# led_board.net
KiCad netlist of a schematic drawn in EAGLE
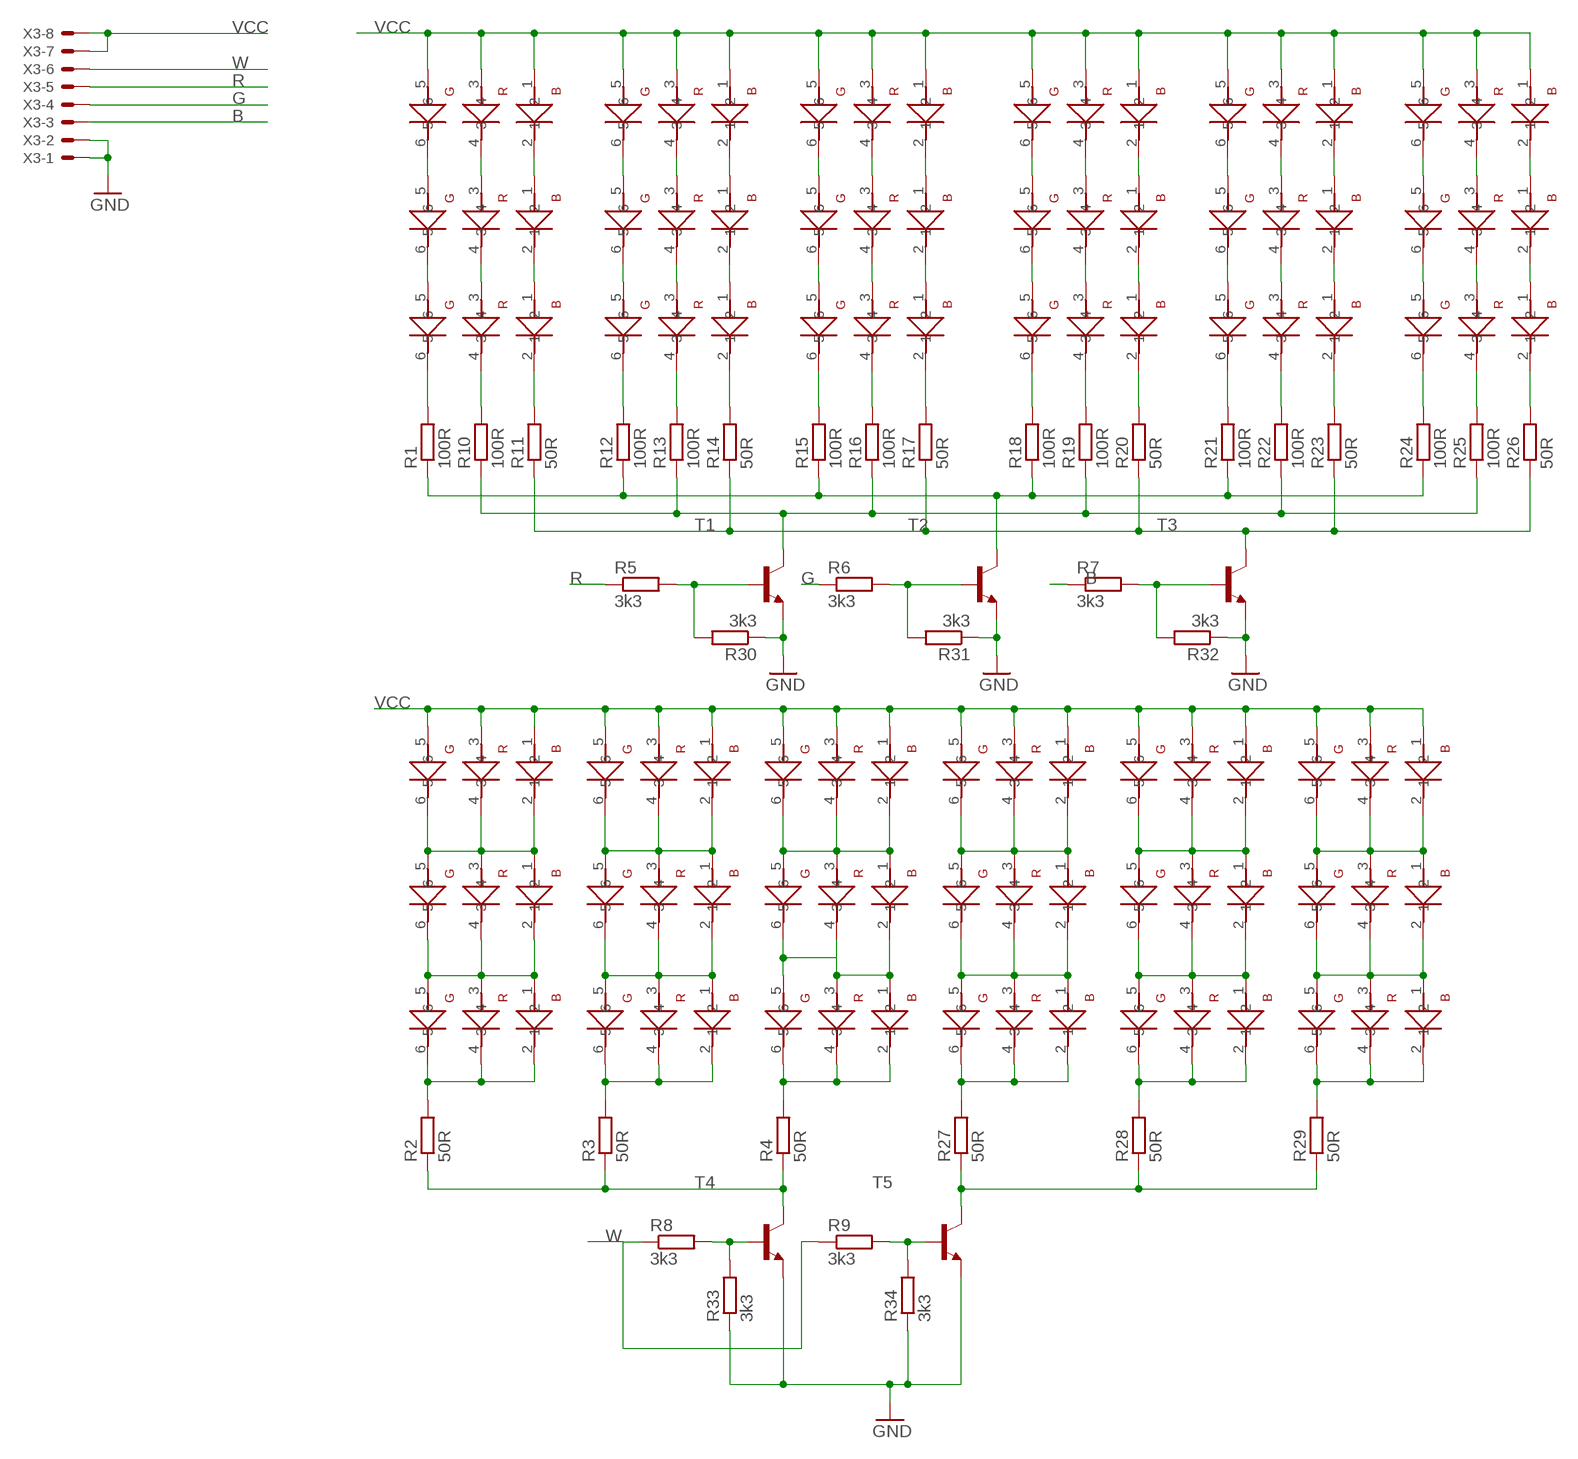
[diagram p0: schematic, sheet 1]

(export (version "E")
  (design (tool "Eeschema 10.0.6"))
  (components
    (comp (ref "R1")
      (value "100R")
      (footprint "eagle-import:M1206")
      (libsource (lib "eagle-import") (part "R-EU_M1206"))
    )
    (comp (ref "R2")
      (value "50R")
      (footprint "eagle-import:M1206")
      (libsource (lib "eagle-import") (part "R-EU_M1206"))
    )
    (comp (ref "R3")
      (value "50R")
      (footprint "eagle-import:M1206")
      (libsource (lib "eagle-import") (part "R-EU_M1206"))
    )
    (comp (ref "R4")
      (value "50R")
      (footprint "eagle-import:M1206")
      (libsource (lib "eagle-import") (part "R-EU_M1206"))
    )
    (comp (ref "R5")
      (value "3k3")
      (footprint "eagle-import:M1206")
      (libsource (lib "eagle-import") (part "R-EU_M1206"))
    )
    (comp (ref "R6")
      (value "3k3")
      (footprint "eagle-import:M1206")
      (libsource (lib "eagle-import") (part "R-EU_M1206"))
    )
    (comp (ref "R7")
      (value "3k3")
      (footprint "eagle-import:M1206")
      (libsource (lib "eagle-import") (part "R-EU_M1206"))
    )
    (comp (ref "R8")
      (value "3k3")
      (footprint "eagle-import:M1206")
      (libsource (lib "eagle-import") (part "R-EU_M1206"))
    )
    (comp (ref "R9")
      (value "3k3")
      (footprint "eagle-import:M1206")
      (libsource (lib "eagle-import") (part "R-EU_M1206"))
    )
    (comp (ref "R10")
      (value "100R")
      (footprint "eagle-import:M1206")
      (libsource (lib "eagle-import") (part "R-EU_M1206"))
    )
    (comp (ref "R11")
      (value "50R")
      (footprint "eagle-import:M1206")
      (libsource (lib "eagle-import") (part "R-EU_M1206"))
    )
    (comp (ref "R12")
      (value "100R")
      (footprint "eagle-import:M1206")
      (libsource (lib "eagle-import") (part "R-EU_M1206"))
    )
    (comp (ref "R13")
      (value "100R")
      (footprint "eagle-import:M1206")
      (libsource (lib "eagle-import") (part "R-EU_M1206"))
    )
    (comp (ref "R14")
      (value "50R")
      (footprint "eagle-import:M1206")
      (libsource (lib "eagle-import") (part "R-EU_M1206"))
    )
    (comp (ref "R15")
      (value "100R")
      (footprint "eagle-import:M1206")
      (libsource (lib "eagle-import") (part "R-EU_M1206"))
    )
    (comp (ref "R16")
      (value "100R")
      (footprint "eagle-import:M1206")
      (libsource (lib "eagle-import") (part "R-EU_M1206"))
    )
    (comp (ref "R17")
      (value "50R")
      (footprint "eagle-import:M1206")
      (libsource (lib "eagle-import") (part "R-EU_M1206"))
    )
    (comp (ref "R18")
      (value "100R")
      (footprint "eagle-import:M1206")
      (libsource (lib "eagle-import") (part "R-EU_M1206"))
    )
    (comp (ref "R19")
      (value "100R")
      (footprint "eagle-import:M1206")
      (libsource (lib "eagle-import") (part "R-EU_M1206"))
    )
    (comp (ref "R20")
      (value "50R")
      (footprint "eagle-import:M1206")
      (libsource (lib "eagle-import") (part "R-EU_M1206"))
    )
    (comp (ref "R21")
      (value "100R")
      (footprint "eagle-import:M1206")
      (libsource (lib "eagle-import") (part "R-EU_M1206"))
    )
    (comp (ref "R22")
      (value "100R")
      (footprint "eagle-import:M1206")
      (libsource (lib "eagle-import") (part "R-EU_M1206"))
    )
    (comp (ref "R23")
      (value "50R")
      (footprint "eagle-import:M1206")
      (libsource (lib "eagle-import") (part "R-EU_M1206"))
    )
    (comp (ref "R24")
      (value "100R")
      (footprint "eagle-import:M1206")
      (libsource (lib "eagle-import") (part "R-EU_M1206"))
    )
    (comp (ref "R25")
      (value "100R")
      (footprint "eagle-import:M1206")
      (libsource (lib "eagle-import") (part "R-EU_M1206"))
    )
    (comp (ref "R26")
      (value "50R")
      (footprint "eagle-import:M1206")
      (libsource (lib "eagle-import") (part "R-EU_M1206"))
    )
    (comp (ref "R27")
      (value "50R")
      (footprint "eagle-import:M1206")
      (libsource (lib "eagle-import") (part "R-EU_M1206"))
    )
    (comp (ref "R28")
      (value "50R")
      (footprint "eagle-import:M1206")
      (libsource (lib "eagle-import") (part "R-EU_M1206"))
    )
    (comp (ref "R29")
      (value "50R")
      (footprint "eagle-import:M1206")
      (libsource (lib "eagle-import") (part "R-EU_M1206"))
    )
    (comp (ref "R30")
      (value "3k3")
      (footprint "eagle-import:M1206")
      (libsource (lib "eagle-import") (part "R-EU_M1206"))
    )
    (comp (ref "R31")
      (value "3k3")
      (footprint "eagle-import:M1206")
      (libsource (lib "eagle-import") (part "R-EU_M1206"))
    )
    (comp (ref "R32")
      (value "3k3")
      (footprint "eagle-import:M1206")
      (libsource (lib "eagle-import") (part "R-EU_M1206"))
    )
    (comp (ref "R33")
      (value "3k3")
      (footprint "eagle-import:M1206")
      (libsource (lib "eagle-import") (part "R-EU_M1206"))
    )
    (comp (ref "R34")
      (value "3k3")
      (footprint "eagle-import:M1206")
      (libsource (lib "eagle-import") (part "R-EU_M1206"))
    )
    (comp (ref "T1")
      (value "-NPN-SOT223")
      (footprint "eagle-import:SOT223")
      (libsource (lib "eagle-import") (part "-NPN-SOT223"))
    )
    (comp (ref "T2")
      (value "-NPN-SOT223")
      (footprint "eagle-import:SOT223")
      (libsource (lib "eagle-import") (part "-NPN-SOT223"))
    )
    (comp (ref "T3")
      (value "-NPN-SOT223")
      (footprint "eagle-import:SOT223")
      (libsource (lib "eagle-import") (part "-NPN-SOT223"))
    )
    (comp (ref "T4")
      (value "-NPN-SOT223")
      (footprint "eagle-import:SOT223")
      (libsource (lib "eagle-import") (part "-NPN-SOT223"))
    )
    (comp (ref "T5")
      (value "-NPN-SOT223")
      (footprint "eagle-import:SOT223")
      (libsource (lib "eagle-import") (part "-NPN-SOT223"))
    )
    (comp (ref "U$1")
      (value "5050_LED")
      (footprint "eagle-import:5050_LED")
      (libsource (lib "eagle-import") (part "5050_LED"))
    )
    (comp (ref "U$2")
      (value "5050_LED")
      (footprint "eagle-import:5050_LED")
      (libsource (lib "eagle-import") (part "5050_LED"))
    )
    (comp (ref "U$3")
      (value "5050_LED")
      (footprint "eagle-import:5050_LED")
      (libsource (lib "eagle-import") (part "5050_LED"))
    )
    (comp (ref "U$4")
      (value "5050_LED")
      (footprint "eagle-import:5050_LED")
      (libsource (lib "eagle-import") (part "5050_LED"))
    )
    (comp (ref "U$5")
      (value "5050_LED")
      (footprint "eagle-import:5050_LED")
      (libsource (lib "eagle-import") (part "5050_LED"))
    )
    (comp (ref "U$6")
      (value "5050_LED")
      (footprint "eagle-import:5050_LED")
      (libsource (lib "eagle-import") (part "5050_LED"))
    )
    (comp (ref "U$7")
      (value "5050_LED")
      (footprint "eagle-import:5050_LED")
      (libsource (lib "eagle-import") (part "5050_LED"))
    )
    (comp (ref "U$8")
      (value "5050_LED")
      (footprint "eagle-import:5050_LED")
      (libsource (lib "eagle-import") (part "5050_LED"))
    )
    (comp (ref "U$9")
      (value "5050_LED")
      (footprint "eagle-import:5050_LED")
      (libsource (lib "eagle-import") (part "5050_LED"))
    )
    (comp (ref "U$10")
      (value "5050_LED")
      (footprint "eagle-import:5050_LED")
      (libsource (lib "eagle-import") (part "5050_LED"))
    )
    (comp (ref "U$11")
      (value "5050_LED")
      (footprint "eagle-import:5050_LED")
      (libsource (lib "eagle-import") (part "5050_LED"))
    )
    (comp (ref "U$12")
      (value "5050_LED")
      (footprint "eagle-import:5050_LED")
      (libsource (lib "eagle-import") (part "5050_LED"))
    )
    (comp (ref "U$13")
      (value "5050_LED")
      (footprint "eagle-import:5050_LED")
      (libsource (lib "eagle-import") (part "5050_LED"))
    )
    (comp (ref "U$14")
      (value "5050_LED")
      (footprint "eagle-import:5050_LED")
      (libsource (lib "eagle-import") (part "5050_LED"))
    )
    (comp (ref "U$15")
      (value "5050_LED")
      (footprint "eagle-import:5050_LED")
      (libsource (lib "eagle-import") (part "5050_LED"))
    )
    (comp (ref "U$16")
      (value "5050_LED")
      (footprint "eagle-import:5050_LED")
      (libsource (lib "eagle-import") (part "5050_LED"))
    )
    (comp (ref "U$17")
      (value "5050_LED")
      (footprint "eagle-import:5050_LED")
      (libsource (lib "eagle-import") (part "5050_LED"))
    )
    (comp (ref "U$18")
      (value "5050_LED")
      (footprint "eagle-import:5050_LED")
      (libsource (lib "eagle-import") (part "5050_LED"))
    )
    (comp (ref "U$19")
      (value "5050_LED")
      (footprint "eagle-import:5050_LED")
      (libsource (lib "eagle-import") (part "5050_LED"))
    )
    (comp (ref "U$20")
      (value "5050_LED")
      (footprint "eagle-import:5050_LED")
      (libsource (lib "eagle-import") (part "5050_LED"))
    )
    (comp (ref "U$21")
      (value "5050_LED")
      (footprint "eagle-import:5050_LED")
      (libsource (lib "eagle-import") (part "5050_LED"))
    )
    (comp (ref "U$22")
      (value "5050_LED")
      (footprint "eagle-import:5050_LED")
      (libsource (lib "eagle-import") (part "5050_LED"))
    )
    (comp (ref "U$23")
      (value "5050_LED")
      (footprint "eagle-import:5050_LED")
      (libsource (lib "eagle-import") (part "5050_LED"))
    )
    (comp (ref "U$24")
      (value "5050_LED")
      (footprint "eagle-import:5050_LED")
      (libsource (lib "eagle-import") (part "5050_LED"))
    )
    (comp (ref "U$25")
      (value "5050_LED")
      (footprint "eagle-import:5050_LED")
      (libsource (lib "eagle-import") (part "5050_LED"))
    )
    (comp (ref "U$26")
      (value "5050_LED")
      (footprint "eagle-import:5050_LED")
      (libsource (lib "eagle-import") (part "5050_LED"))
    )
    (comp (ref "U$27")
      (value "5050_LED")
      (footprint "eagle-import:5050_LED")
      (libsource (lib "eagle-import") (part "5050_LED"))
    )
    (comp (ref "U$28")
      (value "5050_LED")
      (footprint "eagle-import:5050_LED")
      (libsource (lib "eagle-import") (part "5050_LED"))
    )
    (comp (ref "U$29")
      (value "5050_LED")
      (footprint "eagle-import:5050_LED")
      (libsource (lib "eagle-import") (part "5050_LED"))
    )
    (comp (ref "U$30")
      (value "5050_LED")
      (footprint "eagle-import:5050_LED")
      (libsource (lib "eagle-import") (part "5050_LED"))
    )
    (comp (ref "U$31")
      (value "5050_LED")
      (footprint "eagle-import:5050_LED")
      (libsource (lib "eagle-import") (part "5050_LED"))
    )
    (comp (ref "U$32")
      (value "5050_LED")
      (footprint "eagle-import:5050_LED")
      (libsource (lib "eagle-import") (part "5050_LED"))
    )
    (comp (ref "U$33")
      (value "5050_LED")
      (footprint "eagle-import:5050_LED")
      (libsource (lib "eagle-import") (part "5050_LED"))
    )
    (comp (ref "U$34")
      (value "5050_LED")
      (footprint "eagle-import:5050_LED")
      (libsource (lib "eagle-import") (part "5050_LED"))
    )
    (comp (ref "U$35")
      (value "5050_LED")
      (footprint "eagle-import:5050_LED")
      (libsource (lib "eagle-import") (part "5050_LED"))
    )
    (comp (ref "U$38")
      (value "5050_LED")
      (footprint "eagle-import:5050_LED")
      (libsource (lib "eagle-import") (part "5050_LED"))
    )
    (comp (ref "X3")
      (value "KK-156-8")
      (footprint "eagle-import:KK-156-8")
      (fields (field (name "MF") "MOLEX"))
      (libsource (lib "eagle-import") (part "KK-156-8"))
    )
  )
  (nets
    (net (code "1") (name "/B") (class "Default")
      (node (ref "R7") (pin "1") (pinfunction "1_1") (pintype "passive"))
      (node (ref "X3") (pin "3") (pinfunction "S_3") (pintype "passive"))
    )
    (net (code "2") (name "/G") (class "Default")
      (node (ref "R6") (pin "1") (pinfunction "1_1") (pintype "passive"))
      (node (ref "X3") (pin "4") (pinfunction "S_4") (pintype "passive"))
    )
    (net (code "3") (name "/R") (class "Default")
      (node (ref "R5") (pin "1") (pinfunction "1_1") (pintype "passive"))
      (node (ref "X3") (pin "5") (pinfunction "S_5") (pintype "passive"))
    )
    (net (code "4") (name "/VCC") (class "Default")
      (node (ref "U$11") (pin "1") (pinfunction "1_1") (pintype "bidirectional"))
      (node (ref "U$11") (pin "3") (pinfunction "3_3") (pintype "bidirectional"))
      (node (ref "U$11") (pin "5") (pinfunction "5_5") (pintype "bidirectional"))
      (node (ref "U$14") (pin "1") (pinfunction "1_1") (pintype "bidirectional"))
      (node (ref "U$14") (pin "3") (pinfunction "3_3") (pintype "bidirectional"))
      (node (ref "U$14") (pin "5") (pinfunction "5_5") (pintype "bidirectional"))
      (node (ref "U$17") (pin "1") (pinfunction "1_1") (pintype "bidirectional"))
      (node (ref "U$17") (pin "3") (pinfunction "3_3") (pintype "bidirectional"))
      (node (ref "U$17") (pin "5") (pinfunction "5_5") (pintype "bidirectional"))
      (node (ref "U$18") (pin "1") (pinfunction "1_1") (pintype "bidirectional"))
      (node (ref "U$18") (pin "3") (pinfunction "3_3") (pintype "bidirectional"))
      (node (ref "U$18") (pin "5") (pinfunction "5_5") (pintype "bidirectional"))
      (node (ref "U$19") (pin "1") (pinfunction "1_1") (pintype "bidirectional"))
      (node (ref "U$19") (pin "3") (pinfunction "3_3") (pintype "bidirectional"))
      (node (ref "U$19") (pin "5") (pinfunction "5_5") (pintype "bidirectional"))
      (node (ref "U$2") (pin "1") (pinfunction "1_1") (pintype "bidirectional"))
      (node (ref "U$2") (pin "3") (pinfunction "3_3") (pintype "bidirectional"))
      (node (ref "U$2") (pin "5") (pinfunction "5_5") (pintype "bidirectional"))
      (node (ref "U$20") (pin "1") (pinfunction "1_1") (pintype "bidirectional"))
      (node (ref "U$20") (pin "3") (pinfunction "3_3") (pintype "bidirectional"))
      (node (ref "U$20") (pin "5") (pinfunction "5_5") (pintype "bidirectional"))
      (node (ref "U$21") (pin "1") (pinfunction "1_1") (pintype "bidirectional"))
      (node (ref "U$21") (pin "3") (pinfunction "3_3") (pintype "bidirectional"))
      (node (ref "U$21") (pin "5") (pinfunction "5_5") (pintype "bidirectional"))
      (node (ref "U$22") (pin "1") (pinfunction "1_1") (pintype "bidirectional"))
      (node (ref "U$22") (pin "3") (pinfunction "3_3") (pintype "bidirectional"))
      (node (ref "U$22") (pin "5") (pinfunction "5_5") (pintype "bidirectional"))
      (node (ref "U$34") (pin "1") (pinfunction "1_1") (pintype "bidirectional"))
      (node (ref "U$34") (pin "3") (pinfunction "3_3") (pintype "bidirectional"))
      (node (ref "U$34") (pin "5") (pinfunction "5_5") (pintype "bidirectional"))
      (node (ref "U$5") (pin "1") (pinfunction "1_1") (pintype "bidirectional"))
      (node (ref "U$5") (pin "3") (pinfunction "3_3") (pintype "bidirectional"))
      (node (ref "U$5") (pin "5") (pinfunction "5_5") (pintype "bidirectional"))
      (node (ref "U$8") (pin "1") (pinfunction "1_1") (pintype "bidirectional"))
      (node (ref "U$8") (pin "3") (pinfunction "3_3") (pintype "bidirectional"))
      (node (ref "U$8") (pin "5") (pinfunction "5_5") (pintype "bidirectional"))
      (node (ref "X3") (pin "7") (pinfunction "S_7") (pintype "passive"))
      (node (ref "X3") (pin "8") (pinfunction "S_8") (pintype "passive"))
    )
    (net (code "5") (name "/W") (class "Default")
      (node (ref "R8") (pin "1") (pinfunction "1_1") (pintype "passive"))
      (node (ref "R9") (pin "1") (pinfunction "1_1") (pintype "passive"))
      (node (ref "X3") (pin "6") (pinfunction "S_6") (pintype "passive"))
    )
    (net (code "6") (name "GND") (class "Default")
      (node (ref "R30") (pin "1") (pinfunction "1_1") (pintype "passive"))
      (node (ref "R31") (pin "1") (pinfunction "1_1") (pintype "passive"))
      (node (ref "R32") (pin "1") (pinfunction "1_1") (pintype "passive"))
      (node (ref "R33") (pin "1") (pinfunction "1_1") (pintype "passive"))
      (node (ref "R34") (pin "1") (pinfunction "1_1") (pintype "passive"))
      (node (ref "T1") (pin "3") (pinfunction "E_3") (pintype "passive"))
      (node (ref "T2") (pin "3") (pinfunction "E_3") (pintype "passive"))
      (node (ref "T3") (pin "3") (pinfunction "E_3") (pintype "passive"))
      (node (ref "T4") (pin "3") (pinfunction "E_3") (pintype "passive"))
      (node (ref "T5") (pin "3") (pinfunction "E_3") (pintype "passive"))
      (node (ref "X3") (pin "1") (pinfunction "S_1") (pintype "passive"))
      (node (ref "X3") (pin "2") (pinfunction "S_2") (pintype "passive"))
    )
    (net (code "7") (name "Net-(R1-Pad2)") (class "Default")
      (node (ref "R1") (pin "2") (pinfunction "2_2") (pintype "passive"))
      (node (ref "U$1") (pin "6") (pinfunction "6_6") (pintype "bidirectional"))
    )
    (net (code "8") (name "Net-(R2-Pad2)") (class "Default")
      (node (ref "R2") (pin "2") (pinfunction "2_2") (pintype "passive"))
      (node (ref "U$29") (pin "2") (pinfunction "2_2") (pintype "bidirectional"))
      (node (ref "U$29") (pin "4") (pinfunction "4_4") (pintype "bidirectional"))
      (node (ref "U$29") (pin "6") (pinfunction "6_6") (pintype "bidirectional"))
    )
    (net (code "9") (name "Net-(R3-Pad2)") (class "Default")
      (node (ref "R3") (pin "2") (pinfunction "2_2") (pintype "passive"))
      (node (ref "U$30") (pin "2") (pinfunction "2_2") (pintype "bidirectional"))
      (node (ref "U$30") (pin "4") (pinfunction "4_4") (pintype "bidirectional"))
      (node (ref "U$30") (pin "6") (pinfunction "6_6") (pintype "bidirectional"))
    )
    (net (code "10") (name "Net-(R4-Pad2)") (class "Default")
      (node (ref "R4") (pin "2") (pinfunction "2_2") (pintype "passive"))
      (node (ref "U$31") (pin "2") (pinfunction "2_2") (pintype "bidirectional"))
      (node (ref "U$31") (pin "4") (pinfunction "4_4") (pintype "bidirectional"))
      (node (ref "U$31") (pin "6") (pinfunction "6_6") (pintype "bidirectional"))
    )
    (net (code "11") (name "Net-(R10-Pad2)") (class "Default")
      (node (ref "R10") (pin "2") (pinfunction "2_2") (pintype "passive"))
      (node (ref "U$1") (pin "4") (pinfunction "4_4") (pintype "bidirectional"))
    )
    (net (code "12") (name "Net-(R11-Pad2)") (class "Default")
      (node (ref "R11") (pin "2") (pinfunction "2_2") (pintype "passive"))
      (node (ref "U$1") (pin "2") (pinfunction "2_2") (pintype "bidirectional"))
    )
    (net (code "13") (name "Net-(R12-Pad2)") (class "Default")
      (node (ref "R12") (pin "2") (pinfunction "2_2") (pintype "passive"))
      (node (ref "U$4") (pin "6") (pinfunction "6_6") (pintype "bidirectional"))
    )
    (net (code "14") (name "Net-(R13-Pad2)") (class "Default")
      (node (ref "R13") (pin "2") (pinfunction "2_2") (pintype "passive"))
      (node (ref "U$4") (pin "4") (pinfunction "4_4") (pintype "bidirectional"))
    )
    (net (code "15") (name "Net-(R14-Pad2)") (class "Default")
      (node (ref "R14") (pin "2") (pinfunction "2_2") (pintype "passive"))
      (node (ref "U$4") (pin "2") (pinfunction "2_2") (pintype "bidirectional"))
    )
    (net (code "16") (name "Net-(R15-Pad2)") (class "Default")
      (node (ref "R15") (pin "2") (pinfunction "2_2") (pintype "passive"))
      (node (ref "U$7") (pin "6") (pinfunction "6_6") (pintype "bidirectional"))
    )
    (net (code "17") (name "Net-(R16-Pad2)") (class "Default")
      (node (ref "R16") (pin "2") (pinfunction "2_2") (pintype "passive"))
      (node (ref "U$7") (pin "4") (pinfunction "4_4") (pintype "bidirectional"))
    )
    (net (code "18") (name "Net-(R17-Pad2)") (class "Default")
      (node (ref "R17") (pin "2") (pinfunction "2_2") (pintype "passive"))
      (node (ref "U$7") (pin "2") (pinfunction "2_2") (pintype "bidirectional"))
    )
    (net (code "19") (name "Net-(R18-Pad2)") (class "Default")
      (node (ref "R18") (pin "2") (pinfunction "2_2") (pintype "passive"))
      (node (ref "U$10") (pin "6") (pinfunction "6_6") (pintype "bidirectional"))
    )
    (net (code "20") (name "Net-(R19-Pad2)") (class "Default")
      (node (ref "R19") (pin "2") (pinfunction "2_2") (pintype "passive"))
      (node (ref "U$10") (pin "4") (pinfunction "4_4") (pintype "bidirectional"))
    )
    (net (code "21") (name "Net-(R20-Pad2)") (class "Default")
      (node (ref "R20") (pin "2") (pinfunction "2_2") (pintype "passive"))
      (node (ref "U$10") (pin "2") (pinfunction "2_2") (pintype "bidirectional"))
    )
    (net (code "22") (name "Net-(R21-Pad2)") (class "Default")
      (node (ref "R21") (pin "2") (pinfunction "2_2") (pintype "passive"))
      (node (ref "U$13") (pin "6") (pinfunction "6_6") (pintype "bidirectional"))
    )
    (net (code "23") (name "Net-(R22-Pad2)") (class "Default")
      (node (ref "R22") (pin "2") (pinfunction "2_2") (pintype "passive"))
      (node (ref "U$13") (pin "4") (pinfunction "4_4") (pintype "bidirectional"))
    )
    (net (code "24") (name "Net-(R23-Pad2)") (class "Default")
      (node (ref "R23") (pin "2") (pinfunction "2_2") (pintype "passive"))
      (node (ref "U$13") (pin "2") (pinfunction "2_2") (pintype "bidirectional"))
    )
    (net (code "25") (name "Net-(R24-Pad2)") (class "Default")
      (node (ref "R24") (pin "2") (pinfunction "2_2") (pintype "passive"))
      (node (ref "U$16") (pin "6") (pinfunction "6_6") (pintype "bidirectional"))
    )
    (net (code "26") (name "Net-(R25-Pad2)") (class "Default")
      (node (ref "R25") (pin "2") (pinfunction "2_2") (pintype "passive"))
      (node (ref "U$16") (pin "4") (pinfunction "4_4") (pintype "bidirectional"))
    )
    (net (code "27") (name "Net-(R26-Pad2)") (class "Default")
      (node (ref "R26") (pin "2") (pinfunction "2_2") (pintype "passive"))
      (node (ref "U$16") (pin "2") (pinfunction "2_2") (pintype "bidirectional"))
    )
    (net (code "28") (name "Net-(R27-Pad2)") (class "Default")
      (node (ref "R27") (pin "2") (pinfunction "2_2") (pintype "passive"))
      (node (ref "U$32") (pin "2") (pinfunction "2_2") (pintype "bidirectional"))
      (node (ref "U$32") (pin "4") (pinfunction "4_4") (pintype "bidirectional"))
      (node (ref "U$32") (pin "6") (pinfunction "6_6") (pintype "bidirectional"))
    )
    (net (code "29") (name "Net-(R28-Pad2)") (class "Default")
      (node (ref "R28") (pin "2") (pinfunction "2_2") (pintype "passive"))
      (node (ref "U$33") (pin "2") (pinfunction "2_2") (pintype "bidirectional"))
      (node (ref "U$33") (pin "4") (pinfunction "4_4") (pintype "bidirectional"))
      (node (ref "U$33") (pin "6") (pinfunction "6_6") (pintype "bidirectional"))
    )
    (net (code "30") (name "Net-(R29-Pad2)") (class "Default")
      (node (ref "R29") (pin "2") (pinfunction "2_2") (pintype "passive"))
      (node (ref "U$35") (pin "2") (pinfunction "2_2") (pintype "bidirectional"))
      (node (ref "U$35") (pin "4") (pinfunction "4_4") (pintype "bidirectional"))
      (node (ref "U$35") (pin "6") (pinfunction "6_6") (pintype "bidirectional"))
    )
    (net (code "31") (name "Net-(T1-B)") (class "Default")
      (node (ref "R30") (pin "2") (pinfunction "2_2") (pintype "passive"))
      (node (ref "R5") (pin "2") (pinfunction "2_2") (pintype "passive"))
      (node (ref "T1") (pin "1") (pinfunction "B_1") (pintype "passive"))
    )
    (net (code "32") (name "Net-(T1-C)") (class "Default")
      (node (ref "R10") (pin "1") (pinfunction "1_1") (pintype "passive"))
      (node (ref "R13") (pin "1") (pinfunction "1_1") (pintype "passive"))
      (node (ref "R16") (pin "1") (pinfunction "1_1") (pintype "passive"))
      (node (ref "R19") (pin "1") (pinfunction "1_1") (pintype "passive"))
      (node (ref "R22") (pin "1") (pinfunction "1_1") (pintype "passive"))
      (node (ref "R25") (pin "1") (pinfunction "1_1") (pintype "passive"))
      (node (ref "T1") (pin "4") (pinfunction "C_4") (pintype "passive"))
    )
    (net (code "33") (name "Net-(T2-B)") (class "Default")
      (node (ref "R31") (pin "2") (pinfunction "2_2") (pintype "passive"))
      (node (ref "R6") (pin "2") (pinfunction "2_2") (pintype "passive"))
      (node (ref "T2") (pin "1") (pinfunction "B_1") (pintype "passive"))
    )
    (net (code "34") (name "Net-(T2-C)") (class "Default")
      (node (ref "R1") (pin "1") (pinfunction "1_1") (pintype "passive"))
      (node (ref "R12") (pin "1") (pinfunction "1_1") (pintype "passive"))
      (node (ref "R15") (pin "1") (pinfunction "1_1") (pintype "passive"))
      (node (ref "R18") (pin "1") (pinfunction "1_1") (pintype "passive"))
      (node (ref "R21") (pin "1") (pinfunction "1_1") (pintype "passive"))
      (node (ref "R24") (pin "1") (pinfunction "1_1") (pintype "passive"))
      (node (ref "T2") (pin "4") (pinfunction "C_4") (pintype "passive"))
    )
    (net (code "35") (name "Net-(T3-B)") (class "Default")
      (node (ref "R32") (pin "2") (pinfunction "2_2") (pintype "passive"))
      (node (ref "R7") (pin "2") (pinfunction "2_2") (pintype "passive"))
      (node (ref "T3") (pin "1") (pinfunction "B_1") (pintype "passive"))
    )
    (net (code "36") (name "Net-(T3-C)") (class "Default")
      (node (ref "R11") (pin "1") (pinfunction "1_1") (pintype "passive"))
      (node (ref "R14") (pin "1") (pinfunction "1_1") (pintype "passive"))
      (node (ref "R17") (pin "1") (pinfunction "1_1") (pintype "passive"))
      (node (ref "R20") (pin "1") (pinfunction "1_1") (pintype "passive"))
      (node (ref "R23") (pin "1") (pinfunction "1_1") (pintype "passive"))
      (node (ref "R26") (pin "1") (pinfunction "1_1") (pintype "passive"))
      (node (ref "T3") (pin "4") (pinfunction "C_4") (pintype "passive"))
    )
    (net (code "37") (name "Net-(T4-B)") (class "Default")
      (node (ref "R33") (pin "2") (pinfunction "2_2") (pintype "passive"))
      (node (ref "R8") (pin "2") (pinfunction "2_2") (pintype "passive"))
      (node (ref "T4") (pin "1") (pinfunction "B_1") (pintype "passive"))
    )
    (net (code "38") (name "Net-(T4-C)") (class "Default")
      (node (ref "R2") (pin "1") (pinfunction "1_1") (pintype "passive"))
      (node (ref "R3") (pin "1") (pinfunction "1_1") (pintype "passive"))
      (node (ref "R4") (pin "1") (pinfunction "1_1") (pintype "passive"))
      (node (ref "T4") (pin "4") (pinfunction "C_4") (pintype "passive"))
    )
    (net (code "39") (name "Net-(T5-B)") (class "Default")
      (node (ref "R34") (pin "2") (pinfunction "2_2") (pintype "passive"))
      (node (ref "R9") (pin "2") (pinfunction "2_2") (pintype "passive"))
      (node (ref "T5") (pin "1") (pinfunction "B_1") (pintype "passive"))
    )
    (net (code "40") (name "Net-(T5-C)") (class "Default")
      (node (ref "R27") (pin "1") (pinfunction "1_1") (pintype "passive"))
      (node (ref "R28") (pin "1") (pinfunction "1_1") (pintype "passive"))
      (node (ref "R29") (pin "1") (pinfunction "1_1") (pintype "passive"))
      (node (ref "T5") (pin "4") (pinfunction "C_4") (pintype "passive"))
    )
    (net (code "41") (name "Net-(U$1-Pad1)") (class "Default")
      (node (ref "U$1") (pin "1") (pinfunction "1_1") (pintype "bidirectional"))
      (node (ref "U$38") (pin "2") (pinfunction "2_2") (pintype "bidirectional"))
    )
    (net (code "42") (name "Net-(U$1-Pad3)") (class "Default")
      (node (ref "U$1") (pin "3") (pinfunction "3_3") (pintype "bidirectional"))
      (node (ref "U$38") (pin "4") (pinfunction "4_4") (pintype "bidirectional"))
    )
    (net (code "43") (name "Net-(U$1-Pad5)") (class "Default")
      (node (ref "U$1") (pin "5") (pinfunction "5_5") (pintype "bidirectional"))
      (node (ref "U$38") (pin "6") (pinfunction "6_6") (pintype "bidirectional"))
    )
    (net (code "44") (name "Net-(U$2-Pad2)") (class "Default")
      (node (ref "U$2") (pin "2") (pinfunction "2_2") (pintype "bidirectional"))
      (node (ref "U$3") (pin "1") (pinfunction "1_1") (pintype "bidirectional"))
    )
    (net (code "45") (name "Net-(U$2-Pad4)") (class "Default")
      (node (ref "U$2") (pin "4") (pinfunction "4_4") (pintype "bidirectional"))
      (node (ref "U$3") (pin "3") (pinfunction "3_3") (pintype "bidirectional"))
    )
    (net (code "46") (name "Net-(U$2-Pad6)") (class "Default")
      (node (ref "U$2") (pin "6") (pinfunction "6_6") (pintype "bidirectional"))
      (node (ref "U$3") (pin "5") (pinfunction "5_5") (pintype "bidirectional"))
    )
    (net (code "47") (name "Net-(U$3-Pad2)") (class "Default")
      (node (ref "U$3") (pin "2") (pinfunction "2_2") (pintype "bidirectional"))
      (node (ref "U$4") (pin "1") (pinfunction "1_1") (pintype "bidirectional"))
    )
    (net (code "48") (name "Net-(U$3-Pad4)") (class "Default")
      (node (ref "U$3") (pin "4") (pinfunction "4_4") (pintype "bidirectional"))
      (node (ref "U$4") (pin "3") (pinfunction "3_3") (pintype "bidirectional"))
    )
    (net (code "49") (name "Net-(U$3-Pad6)") (class "Default")
      (node (ref "U$3") (pin "6") (pinfunction "6_6") (pintype "bidirectional"))
      (node (ref "U$4") (pin "5") (pinfunction "5_5") (pintype "bidirectional"))
    )
    (net (code "50") (name "Net-(U$5-Pad2)") (class "Default")
      (node (ref "U$5") (pin "2") (pinfunction "2_2") (pintype "bidirectional"))
      (node (ref "U$6") (pin "1") (pinfunction "1_1") (pintype "bidirectional"))
    )
    (net (code "51") (name "Net-(U$5-Pad4)") (class "Default")
      (node (ref "U$5") (pin "4") (pinfunction "4_4") (pintype "bidirectional"))
      (node (ref "U$6") (pin "3") (pinfunction "3_3") (pintype "bidirectional"))
    )
    (net (code "52") (name "Net-(U$5-Pad6)") (class "Default")
      (node (ref "U$5") (pin "6") (pinfunction "6_6") (pintype "bidirectional"))
      (node (ref "U$6") (pin "5") (pinfunction "5_5") (pintype "bidirectional"))
    )
    (net (code "53") (name "Net-(U$6-Pad2)") (class "Default")
      (node (ref "U$6") (pin "2") (pinfunction "2_2") (pintype "bidirectional"))
      (node (ref "U$7") (pin "1") (pinfunction "1_1") (pintype "bidirectional"))
    )
    (net (code "54") (name "Net-(U$6-Pad4)") (class "Default")
      (node (ref "U$6") (pin "4") (pinfunction "4_4") (pintype "bidirectional"))
      (node (ref "U$7") (pin "3") (pinfunction "3_3") (pintype "bidirectional"))
    )
    (net (code "55") (name "Net-(U$6-Pad6)") (class "Default")
      (node (ref "U$6") (pin "6") (pinfunction "6_6") (pintype "bidirectional"))
      (node (ref "U$7") (pin "5") (pinfunction "5_5") (pintype "bidirectional"))
    )
    (net (code "56") (name "Net-(U$8-Pad2)") (class "Default")
      (node (ref "U$8") (pin "2") (pinfunction "2_2") (pintype "bidirectional"))
      (node (ref "U$9") (pin "1") (pinfunction "1_1") (pintype "bidirectional"))
    )
    (net (code "57") (name "Net-(U$8-Pad4)") (class "Default")
      (node (ref "U$8") (pin "4") (pinfunction "4_4") (pintype "bidirectional"))
      (node (ref "U$9") (pin "3") (pinfunction "3_3") (pintype "bidirectional"))
    )
    (net (code "58") (name "Net-(U$8-Pad6)") (class "Default")
      (node (ref "U$8") (pin "6") (pinfunction "6_6") (pintype "bidirectional"))
      (node (ref "U$9") (pin "5") (pinfunction "5_5") (pintype "bidirectional"))
    )
    (net (code "59") (name "Net-(U$10-Pad1)") (class "Default")
      (node (ref "U$10") (pin "1") (pinfunction "1_1") (pintype "bidirectional"))
      (node (ref "U$9") (pin "2") (pinfunction "2_2") (pintype "bidirectional"))
    )
    (net (code "60") (name "Net-(U$10-Pad3)") (class "Default")
      (node (ref "U$10") (pin "3") (pinfunction "3_3") (pintype "bidirectional"))
      (node (ref "U$9") (pin "4") (pinfunction "4_4") (pintype "bidirectional"))
    )
    (net (code "61") (name "Net-(U$10-Pad5)") (class "Default")
      (node (ref "U$10") (pin "5") (pinfunction "5_5") (pintype "bidirectional"))
      (node (ref "U$9") (pin "6") (pinfunction "6_6") (pintype "bidirectional"))
    )
    (net (code "62") (name "Net-(U$11-Pad2)") (class "Default")
      (node (ref "U$11") (pin "2") (pinfunction "2_2") (pintype "bidirectional"))
      (node (ref "U$12") (pin "1") (pinfunction "1_1") (pintype "bidirectional"))
    )
    (net (code "63") (name "Net-(U$11-Pad4)") (class "Default")
      (node (ref "U$11") (pin "4") (pinfunction "4_4") (pintype "bidirectional"))
      (node (ref "U$12") (pin "3") (pinfunction "3_3") (pintype "bidirectional"))
    )
    (net (code "64") (name "Net-(U$11-Pad6)") (class "Default")
      (node (ref "U$11") (pin "6") (pinfunction "6_6") (pintype "bidirectional"))
      (node (ref "U$12") (pin "5") (pinfunction "5_5") (pintype "bidirectional"))
    )
    (net (code "65") (name "Net-(U$12-Pad2)") (class "Default")
      (node (ref "U$12") (pin "2") (pinfunction "2_2") (pintype "bidirectional"))
      (node (ref "U$13") (pin "1") (pinfunction "1_1") (pintype "bidirectional"))
    )
    (net (code "66") (name "Net-(U$12-Pad4)") (class "Default")
      (node (ref "U$12") (pin "4") (pinfunction "4_4") (pintype "bidirectional"))
      (node (ref "U$13") (pin "3") (pinfunction "3_3") (pintype "bidirectional"))
    )
    (net (code "67") (name "Net-(U$12-Pad6)") (class "Default")
      (node (ref "U$12") (pin "6") (pinfunction "6_6") (pintype "bidirectional"))
      (node (ref "U$13") (pin "5") (pinfunction "5_5") (pintype "bidirectional"))
    )
    (net (code "68") (name "Net-(U$14-Pad2)") (class "Default")
      (node (ref "U$14") (pin "2") (pinfunction "2_2") (pintype "bidirectional"))
      (node (ref "U$15") (pin "1") (pinfunction "1_1") (pintype "bidirectional"))
    )
    (net (code "69") (name "Net-(U$14-Pad4)") (class "Default")
      (node (ref "U$14") (pin "4") (pinfunction "4_4") (pintype "bidirectional"))
      (node (ref "U$15") (pin "3") (pinfunction "3_3") (pintype "bidirectional"))
    )
    (net (code "70") (name "Net-(U$14-Pad6)") (class "Default")
      (node (ref "U$14") (pin "6") (pinfunction "6_6") (pintype "bidirectional"))
      (node (ref "U$15") (pin "5") (pinfunction "5_5") (pintype "bidirectional"))
    )
    (net (code "71") (name "Net-(U$15-Pad2)") (class "Default")
      (node (ref "U$15") (pin "2") (pinfunction "2_2") (pintype "bidirectional"))
      (node (ref "U$16") (pin "1") (pinfunction "1_1") (pintype "bidirectional"))
    )
    (net (code "72") (name "Net-(U$15-Pad4)") (class "Default")
      (node (ref "U$15") (pin "4") (pinfunction "4_4") (pintype "bidirectional"))
      (node (ref "U$16") (pin "3") (pinfunction "3_3") (pintype "bidirectional"))
    )
    (net (code "73") (name "Net-(U$15-Pad6)") (class "Default")
      (node (ref "U$15") (pin "6") (pinfunction "6_6") (pintype "bidirectional"))
      (node (ref "U$16") (pin "5") (pinfunction "5_5") (pintype "bidirectional"))
    )
    (net (code "74") (name "Net-(U$17-Pad2)") (class "Default")
      (node (ref "U$17") (pin "2") (pinfunction "2_2") (pintype "bidirectional"))
      (node (ref "U$17") (pin "4") (pinfunction "4_4") (pintype "bidirectional"))
      (node (ref "U$17") (pin "6") (pinfunction "6_6") (pintype "bidirectional"))
      (node (ref "U$23") (pin "1") (pinfunction "1_1") (pintype "bidirectional"))
      (node (ref "U$23") (pin "3") (pinfunction "3_3") (pintype "bidirectional"))
      (node (ref "U$23") (pin "5") (pinfunction "5_5") (pintype "bidirectional"))
    )
    (net (code "75") (name "Net-(U$18-Pad2)") (class "Default")
      (node (ref "U$18") (pin "2") (pinfunction "2_2") (pintype "bidirectional"))
      (node (ref "U$18") (pin "4") (pinfunction "4_4") (pintype "bidirectional"))
      (node (ref "U$18") (pin "6") (pinfunction "6_6") (pintype "bidirectional"))
      (node (ref "U$24") (pin "1") (pinfunction "1_1") (pintype "bidirectional"))
      (node (ref "U$24") (pin "3") (pinfunction "3_3") (pintype "bidirectional"))
      (node (ref "U$24") (pin "5") (pinfunction "5_5") (pintype "bidirectional"))
    )
    (net (code "76") (name "Net-(U$19-Pad2)") (class "Default")
      (node (ref "U$19") (pin "2") (pinfunction "2_2") (pintype "bidirectional"))
      (node (ref "U$19") (pin "4") (pinfunction "4_4") (pintype "bidirectional"))
      (node (ref "U$19") (pin "6") (pinfunction "6_6") (pintype "bidirectional"))
      (node (ref "U$25") (pin "1") (pinfunction "1_1") (pintype "bidirectional"))
      (node (ref "U$25") (pin "3") (pinfunction "3_3") (pintype "bidirectional"))
      (node (ref "U$25") (pin "5") (pinfunction "5_5") (pintype "bidirectional"))
    )
    (net (code "77") (name "Net-(U$20-Pad2)") (class "Default")
      (node (ref "U$20") (pin "2") (pinfunction "2_2") (pintype "bidirectional"))
      (node (ref "U$20") (pin "4") (pinfunction "4_4") (pintype "bidirectional"))
      (node (ref "U$20") (pin "6") (pinfunction "6_6") (pintype "bidirectional"))
      (node (ref "U$26") (pin "1") (pinfunction "1_1") (pintype "bidirectional"))
      (node (ref "U$26") (pin "3") (pinfunction "3_3") (pintype "bidirectional"))
      (node (ref "U$26") (pin "5") (pinfunction "5_5") (pintype "bidirectional"))
    )
    (net (code "78") (name "Net-(U$21-Pad2)") (class "Default")
      (node (ref "U$21") (pin "2") (pinfunction "2_2") (pintype "bidirectional"))
      (node (ref "U$21") (pin "4") (pinfunction "4_4") (pintype "bidirectional"))
      (node (ref "U$21") (pin "6") (pinfunction "6_6") (pintype "bidirectional"))
      (node (ref "U$27") (pin "1") (pinfunction "1_1") (pintype "bidirectional"))
      (node (ref "U$27") (pin "3") (pinfunction "3_3") (pintype "bidirectional"))
      (node (ref "U$27") (pin "5") (pinfunction "5_5") (pintype "bidirectional"))
    )
    (net (code "79") (name "Net-(U$22-Pad2)") (class "Default")
      (node (ref "U$22") (pin "2") (pinfunction "2_2") (pintype "bidirectional"))
      (node (ref "U$22") (pin "4") (pinfunction "4_4") (pintype "bidirectional"))
      (node (ref "U$22") (pin "6") (pinfunction "6_6") (pintype "bidirectional"))
      (node (ref "U$28") (pin "1") (pinfunction "1_1") (pintype "bidirectional"))
      (node (ref "U$28") (pin "3") (pinfunction "3_3") (pintype "bidirectional"))
      (node (ref "U$28") (pin "5") (pinfunction "5_5") (pintype "bidirectional"))
    )
    (net (code "80") (name "Net-(U$23-Pad2)") (class "Default")
      (node (ref "U$23") (pin "2") (pinfunction "2_2") (pintype "bidirectional"))
      (node (ref "U$23") (pin "4") (pinfunction "4_4") (pintype "bidirectional"))
      (node (ref "U$23") (pin "6") (pinfunction "6_6") (pintype "bidirectional"))
      (node (ref "U$29") (pin "1") (pinfunction "1_1") (pintype "bidirectional"))
      (node (ref "U$29") (pin "3") (pinfunction "3_3") (pintype "bidirectional"))
      (node (ref "U$29") (pin "5") (pinfunction "5_5") (pintype "bidirectional"))
    )
    (net (code "81") (name "Net-(U$24-Pad2)") (class "Default")
      (node (ref "U$24") (pin "2") (pinfunction "2_2") (pintype "bidirectional"))
      (node (ref "U$24") (pin "4") (pinfunction "4_4") (pintype "bidirectional"))
      (node (ref "U$24") (pin "6") (pinfunction "6_6") (pintype "bidirectional"))
      (node (ref "U$30") (pin "1") (pinfunction "1_1") (pintype "bidirectional"))
      (node (ref "U$30") (pin "3") (pinfunction "3_3") (pintype "bidirectional"))
      (node (ref "U$30") (pin "5") (pinfunction "5_5") (pintype "bidirectional"))
    )
    (net (code "82") (name "Net-(U$25-Pad2)") (class "Default")
      (node (ref "U$25") (pin "2") (pinfunction "2_2") (pintype "bidirectional"))
      (node (ref "U$25") (pin "4") (pinfunction "4_4") (pintype "bidirectional"))
      (node (ref "U$25") (pin "6") (pinfunction "6_6") (pintype "bidirectional"))
      (node (ref "U$31") (pin "1") (pinfunction "1_1") (pintype "bidirectional"))
      (node (ref "U$31") (pin "3") (pinfunction "3_3") (pintype "bidirectional"))
      (node (ref "U$31") (pin "5") (pinfunction "5_5") (pintype "bidirectional"))
    )
    (net (code "83") (name "Net-(U$26-Pad2)") (class "Default")
      (node (ref "U$26") (pin "2") (pinfunction "2_2") (pintype "bidirectional"))
      (node (ref "U$26") (pin "4") (pinfunction "4_4") (pintype "bidirectional"))
      (node (ref "U$26") (pin "6") (pinfunction "6_6") (pintype "bidirectional"))
      (node (ref "U$32") (pin "1") (pinfunction "1_1") (pintype "bidirectional"))
      (node (ref "U$32") (pin "3") (pinfunction "3_3") (pintype "bidirectional"))
      (node (ref "U$32") (pin "5") (pinfunction "5_5") (pintype "bidirectional"))
    )
    (net (code "84") (name "Net-(U$27-Pad2)") (class "Default")
      (node (ref "U$27") (pin "2") (pinfunction "2_2") (pintype "bidirectional"))
      (node (ref "U$27") (pin "4") (pinfunction "4_4") (pintype "bidirectional"))
      (node (ref "U$27") (pin "6") (pinfunction "6_6") (pintype "bidirectional"))
      (node (ref "U$33") (pin "1") (pinfunction "1_1") (pintype "bidirectional"))
      (node (ref "U$33") (pin "3") (pinfunction "3_3") (pintype "bidirectional"))
      (node (ref "U$33") (pin "5") (pinfunction "5_5") (pintype "bidirectional"))
    )
    (net (code "85") (name "Net-(U$28-Pad2)") (class "Default")
      (node (ref "U$28") (pin "2") (pinfunction "2_2") (pintype "bidirectional"))
      (node (ref "U$28") (pin "4") (pinfunction "4_4") (pintype "bidirectional"))
      (node (ref "U$28") (pin "6") (pinfunction "6_6") (pintype "bidirectional"))
      (node (ref "U$35") (pin "1") (pinfunction "1_1") (pintype "bidirectional"))
      (node (ref "U$35") (pin "3") (pinfunction "3_3") (pintype "bidirectional"))
      (node (ref "U$35") (pin "5") (pinfunction "5_5") (pintype "bidirectional"))
    )
    (net (code "86") (name "Net-(U$34-Pad2)") (class "Default")
      (node (ref "U$34") (pin "2") (pinfunction "2_2") (pintype "bidirectional"))
      (node (ref "U$38") (pin "1") (pinfunction "1_1") (pintype "bidirectional"))
    )
    (net (code "87") (name "Net-(U$34-Pad4)") (class "Default")
      (node (ref "U$34") (pin "4") (pinfunction "4_4") (pintype "bidirectional"))
      (node (ref "U$38") (pin "3") (pinfunction "3_3") (pintype "bidirectional"))
    )
    (net (code "88") (name "Net-(U$34-Pad6)") (class "Default")
      (node (ref "U$34") (pin "6") (pinfunction "6_6") (pintype "bidirectional"))
      (node (ref "U$38") (pin "5") (pinfunction "5_5") (pintype "bidirectional"))
    )
  )
)
